# Power.net
KiCad netlist of a schematic drawn in Altium Designer
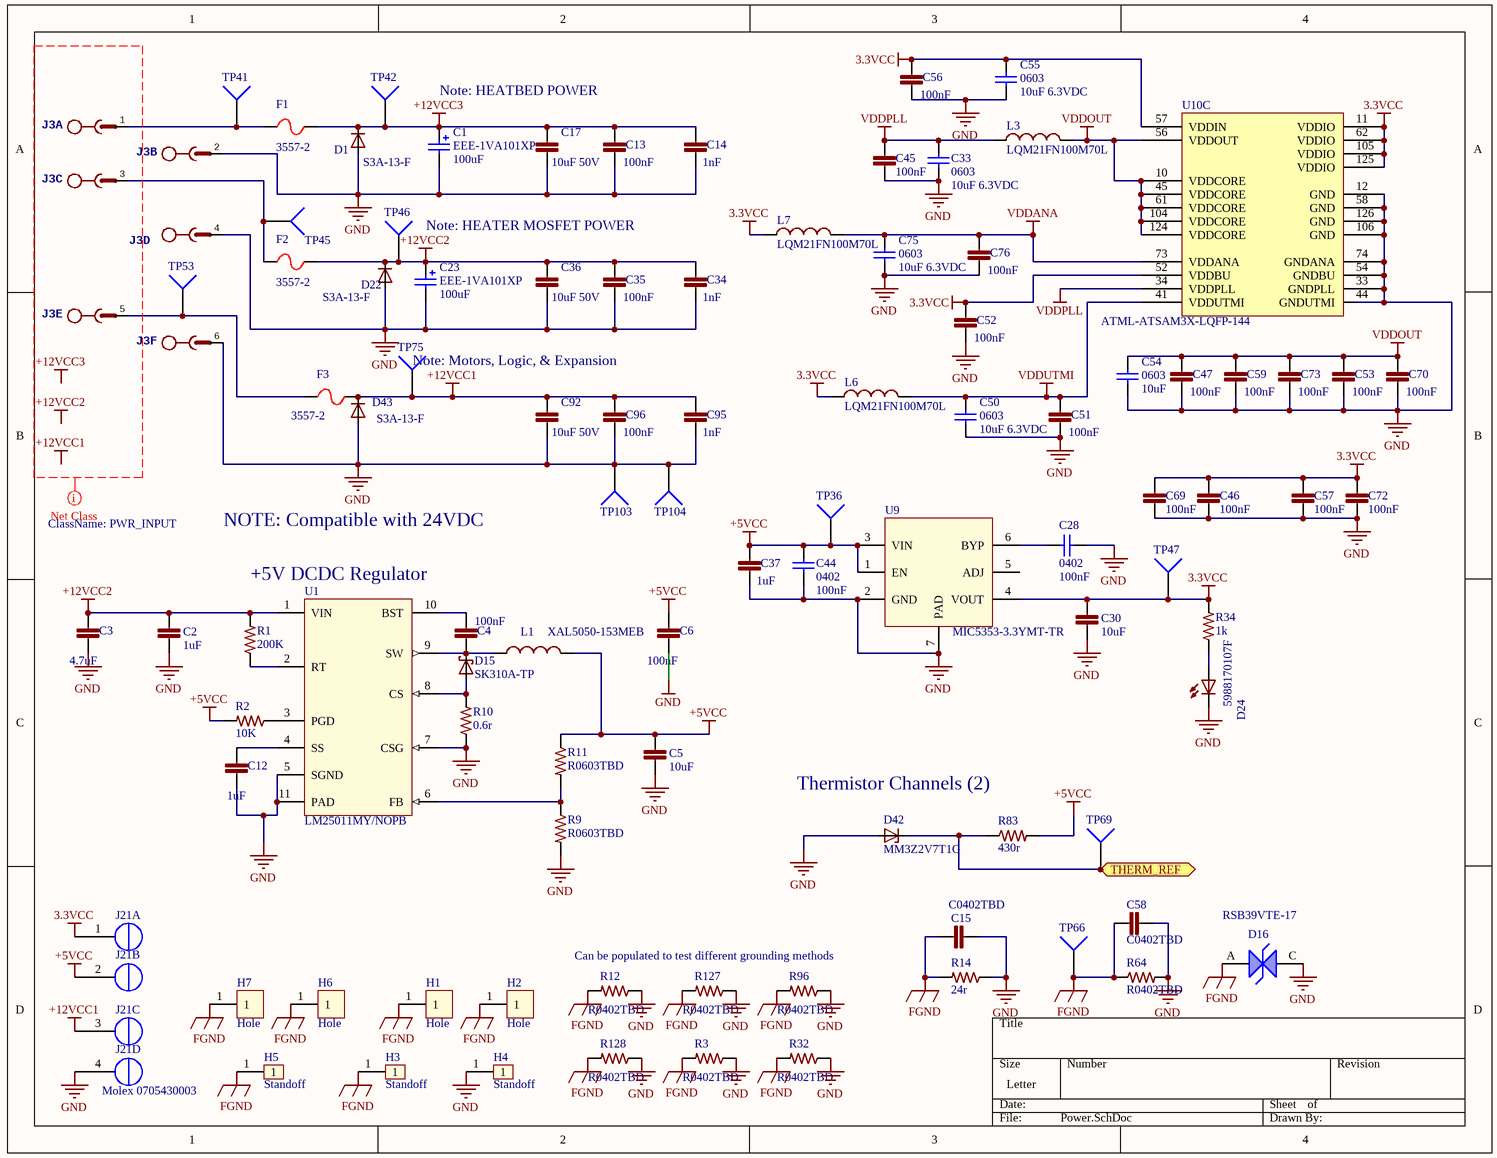
[diagram p0: Power.SchDoc]

(export (version "E")
  (design (tool "Eeschema 10.0.6"))
  (components
    (comp (ref "C1")
      (value "EEE-1VA101XP")
      (footprint "EEE-1VA101XP")
      (description "CAP ALUM 100UF 35V 20% SMD")
      (fields (field (name "DIGIKEY PART #") "PCE3951CT-ND") (field (name "ALTIUM_VALUE") "100uF"))
      (libsource (lib "Tigershark3D") (part "EEE-1VA101XP"))
    )
    (comp (ref "C2")
      (value "1uF")
      (footprint "C0805")
      (description "CAP CER 0805 1uF 50V 10% X7R")
      (fields
        (field (name "MANUFACTURERPARTNUMBER") "GRM21BR71H105KA12L")
        (field (name "PUBLISHER") "UltiMachine")
      )
      (libsource (lib "3Delight") (part "GRM21BR71H105KA12L"))
    )
    (comp (ref "C3")
      (value "4.7uF")
      (footprint "C1206")
      (description "CAP CER 1206 4.7uF 50V 10% X5R")
      (fields
        (field (name "MANUFACTURERPARTNUMBER") "C1206C475K5PACTU")
        (field (name "PUBLISHER") "UltiMachine")
      )
      (libsource (lib "3Delight") (part "C1206C475K5PACTU"))
    )
    (comp (ref "C4")
      (value "100nF")
      (footprint "C0603")
      (description "CAP CER 0603 100nF 50V 10% X7R")
      (fields
        (field (name "MANUFACTURERPARTNUMBER") "C0603C104K5RACTU")
        (field (name "PUBLISHER") "UltiMachine")
      )
      (libsource (lib "3Delight") (part "C0603C104K5RACTU"))
    )
    (comp (ref "C5")
      (value "10uF")
      (footprint "C0805")
      (description "CAP CER 0805 10uF 10V 10% X5R")
      (fields
        (field (name "MANUFACTURERPARTNUMBER") "C0805C106K8PACTU")
        (field (name "PUBLISHER") "UltiMachine")
      )
      (libsource (lib "3Delight") (part "C0805C106K8PACTU"))
    )
    (comp (ref "C6")
      (value "100nF")
      (footprint "C0402")
      (description "CAP CER 0402 100nF 16V 10% X7R")
      (fields
        (field (name "MANUFACTURERPARTNUMBER") "GRM155R71C104KA88D")
        (field (name "PUBLISHER") "UltiMachine")
      )
      (libsource (lib "") (part "GRM155R71C104KA88D_2"))
    )
    (comp (ref "C12")
      (value "1uF")
      (footprint "C0402")
      (description "CAP CER 0402 1uF 6.3V 10% X5R")
      (fields
        (field (name "MANUFACTURERPARTNUMBER") "GRM155R60J105KE19D")
        (field (name "PUBLISHER") "UltiMachine")
      )
      (libsource (lib "3Delight") (part "GRM155R60J105KE19D"))
    )
    (comp (ref "C13")
      (value "100nF")
      (footprint "C0603")
      (description "CAP CER 0603 100nF 50V 10% X7R")
      (fields
        (field (name "MANUFACTURERPARTNUMBER") "C0603C104K5RACTU")
        (field (name "PUBLISHER") "UltiMachine")
      )
      (libsource (lib "3Delight") (part "C0603C104K5RACTU"))
    )
    (comp (ref "C14")
      (value "1nF")
      (footprint "C0603")
      (description "CAP CER 0603  1nF 50v 10% X7R")
      (fields
        (field (name "MANUFACTURERPARTNUMBER") "C0603C102K5RACTU")
        (field (name "PUBLISHER") "UltiMachine")
      )
      (libsource (lib "3Delight") (part "C0603C102K5RACTU"))
    )
    (comp (ref "C15")
      (value "C0402TBD")
      (footprint "C0402")
      (description "Capacitor Non Polarized")
      (fields (field (name "PUBLISHER") "UltiMachine"))
      (libsource (lib "3Delight") (part "C0402TBD"))
    )
    (comp (ref "C17")
      (value "10uF 50V")
      (footprint "C1206")
      (description "CAP CER 10UF 50V 10% X5R 1206")
      (fields
        (field (name "MANUFACTURER") "Samsung")
        (field (name "MANUFACTURERPARTNUMBER") "CL31A106KBHNNNE")
        (field (name "PUBLISHER") "UltiMachine")
      )
      (libsource (lib "Tigershark3D") (part "CL31A106KBHNNNE"))
    )
    (comp (ref "C23")
      (value "EEE-1VA101XP")
      (footprint "EEE-1VA101XP")
      (description "CAP ALUM 100UF 35V 20% SMD")
      (fields (field (name "DIGIKEY PART #") "PCE3951CT-ND") (field (name "ALTIUM_VALUE") "100uF"))
      (libsource (lib "Tigershark3D") (part "EEE-1VA101XP"))
    )
    (comp (ref "C28")
      (value "100nF")
      (footprint "3Delight:C0402")
      (description "Capacitor (Semiconductor SIM Model)")
      (fields
        (field (name "MFR PART #") "GRM155R71C104KA88D")
        (field (name "MFR") "Murata")
        (field (name "PACKAGEREFERENCE") "0402")
        (field (name "PUBLISHER") "Ultimachine")
      )
      (libsource (lib "") (part "GRM155R71C104KA88D_1"))
    )
    (comp (ref "C30")
      (value "10uF")
      (footprint "C0805")
      (description "CAP CER 0805 10uF 10V 10% X5R")
      (fields
        (field (name "MANUFACTURERPARTNUMBER") "C0805C106K8PACTU")
        (field (name "PUBLISHER") "UltiMachine")
      )
      (libsource (lib "3Delight") (part "C0805C106K8PACTU"))
    )
    (comp (ref "C33")
      (value "0603")
      (footprint "C0603")
      (description "CAP CER 10UF 6.3V 10% JB 0603")
      (fields
        (field (name "MFR PART #") "C1608JB0J106K080AB")
        (field (name "MFR") "TDK")
        (field (name "ALTIUM_VALUE") "10uF 6.3VDC")
      )
      (libsource (lib "Tigershark3D") (part "C1608JB0J106K080AB"))
    )
    (comp (ref "C34")
      (value "1nF")
      (footprint "C0603")
      (description "CAP CER 0603  1nF 50v 10% X7R")
      (fields
        (field (name "MANUFACTURERPARTNUMBER") "C0603C102K5RACTU")
        (field (name "PUBLISHER") "UltiMachine")
      )
      (libsource (lib "3Delight") (part "C0603C102K5RACTU"))
    )
    (comp (ref "C35")
      (value "100nF")
      (footprint "C0603")
      (description "CAP CER 0603 100nF 50V 10% X7R")
      (fields
        (field (name "MANUFACTURERPARTNUMBER") "C0603C104K5RACTU")
        (field (name "PUBLISHER") "UltiMachine")
      )
      (libsource (lib "3Delight") (part "C0603C104K5RACTU"))
    )
    (comp (ref "C36")
      (value "10uF 50V")
      (footprint "C1206")
      (description "CAP CER 10UF 50V 10% X5R 1206")
      (fields
        (field (name "MANUFACTURER") "Samsung")
        (field (name "MANUFACTURERPARTNUMBER") "CL31A106KBHNNNE")
        (field (name "PUBLISHER") "UltiMachine")
      )
      (libsource (lib "Tigershark3D") (part "CL31A106KBHNNNE"))
    )
    (comp (ref "C37")
      (value "1uF")
      (footprint "C0402")
      (description "CAP CER 0402 1uF 6.3V 10% X5R")
      (fields
        (field (name "MANUFACTURERPARTNUMBER") "GRM155R60J105KE19D")
        (field (name "PUBLISHER") "UltiMachine")
      )
      (libsource (lib "3Delight") (part "GRM155R60J105KE19D"))
    )
    (comp (ref "C44")
      (value "100nF")
      (footprint "3Delight:C0402")
      (description "Capacitor (Semiconductor SIM Model)")
      (fields
        (field (name "MFR PART #") "GRM155R71C104KA88D")
        (field (name "MFR") "Murata")
        (field (name "PACKAGEREFERENCE") "0402")
        (field (name "PUBLISHER") "Ultimachine")
      )
      (libsource (lib "") (part "GRM155R71C104KA88D_1"))
    )
    (comp (ref "C45")
      (value "100nF")
      (footprint "C0402")
      (description "CAP CER 0402 100nF 16V 10% X7R")
      (fields
        (field (name "MANUFACTURERPARTNUMBER") "GRM155R71C104KA88D")
        (field (name "PUBLISHER") "UltiMachine")
      )
      (libsource (lib "") (part "GRM155R71C104KA88D_3"))
    )
    (comp (ref "C46")
      (value "100nF")
      (footprint "C0402")
      (description "CAP CER 0402 100nF 16V 10% X7R")
      (fields
        (field (name "MANUFACTURERPARTNUMBER") "GRM155R71C104KA88D")
        (field (name "PUBLISHER") "UltiMachine")
      )
      (libsource (lib "") (part "GRM155R71C104KA88D_3"))
    )
    (comp (ref "C47")
      (value "100nF")
      (footprint "C0402")
      (description "CAP CER 0402 100nF 16V 10% X7R")
      (fields
        (field (name "MANUFACTURERPARTNUMBER") "GRM155R71C104KA88D")
        (field (name "PUBLISHER") "UltiMachine")
      )
      (libsource (lib "3Delight") (part "GRM155R71C104KA88D"))
    )
    (comp (ref "C50")
      (value "0603")
      (footprint "C0603")
      (description "CAP CER 10UF 6.3V 10% JB 0603")
      (fields
        (field (name "MFR PART #") "C1608JB0J106K080AB")
        (field (name "MFR") "TDK")
        (field (name "ALTIUM_VALUE") "10uF 6.3VDC")
      )
      (libsource (lib "Tigershark3D") (part "C1608JB0J106K080AB"))
    )
    (comp (ref "C51")
      (value "100nF")
      (footprint "C0402")
      (description "CAP CER 0402 100nF 16V 10% X7R")
      (fields
        (field (name "MANUFACTURERPARTNUMBER") "GRM155R71C104KA88D")
        (field (name "PUBLISHER") "UltiMachine")
      )
      (libsource (lib "3Delight") (part "GRM155R71C104KA88D"))
    )
    (comp (ref "C52")
      (value "100nF")
      (footprint "C0402")
      (description "CAP CER 0402 100nF 16V 10% X7R")
      (fields
        (field (name "MANUFACTURERPARTNUMBER") "GRM155R71C104KA88D")
        (field (name "PUBLISHER") "UltiMachine")
      )
      (libsource (lib "3Delight") (part "GRM155R71C104KA88D"))
    )
    (comp (ref "C53")
      (value "100nF")
      (footprint "C0402")
      (description "CAP CER 0402 100nF 16V 10% X7R")
      (fields
        (field (name "MANUFACTURERPARTNUMBER") "GRM155R71C104KA88D")
        (field (name "PUBLISHER") "UltiMachine")
      )
      (libsource (lib "3Delight") (part "GRM155R71C104KA88D"))
    )
    (comp (ref "C54")
      (value "0603")
      (footprint "C0603")
      (description "CAP CER 10UF 6.3V 10% JB 0603")
      (fields
        (field (name "MFR PART #") "C1608JB0J106K080AB")
        (field (name "MFR") "TDK")
        (field (name "ALTIUM_VALUE") "10uF")
      )
      (libsource (lib "Tigershark3D") (part "C1608JB0J106K080AB"))
    )
    (comp (ref "C55")
      (value "0603")
      (footprint "C0603")
      (description "CAP CER 10UF 6.3V 10% JB 0603")
      (fields
        (field (name "MFR PART #") "C1608JB0J106K080AB")
        (field (name "MFR") "TDK")
        (field (name "ALTIUM_VALUE") "10uF 6.3VDC")
      )
      (libsource (lib "Tigershark3D") (part "C1608JB0J106K080AB"))
    )
    (comp (ref "C56")
      (value "100nF")
      (footprint "C0402")
      (description "CAP CER 0402 100nF 16V 10% X7R")
      (fields
        (field (name "MANUFACTURERPARTNUMBER") "GRM155R71C104KA88D")
        (field (name "PUBLISHER") "UltiMachine")
      )
      (libsource (lib "3Delight") (part "GRM155R71C104KA88D"))
    )
    (comp (ref "C57")
      (value "100nF")
      (footprint "C0402")
      (description "CAP CER 0402 100nF 16V 10% X7R")
      (fields
        (field (name "MANUFACTURERPARTNUMBER") "GRM155R71C104KA88D")
        (field (name "PUBLISHER") "UltiMachine")
      )
      (libsource (lib "") (part "GRM155R71C104KA88D_3"))
    )
    (comp (ref "C58")
      (value "C0402TBD")
      (footprint "C0402")
      (description "Capacitor Non Polarized")
      (fields (field (name "PUBLISHER") "UltiMachine"))
      (libsource (lib "3Delight") (part "C0402TBD"))
    )
    (comp (ref "C59")
      (value "100nF")
      (footprint "C0402")
      (description "CAP CER 0402 100nF 16V 10% X7R")
      (fields
        (field (name "MANUFACTURERPARTNUMBER") "GRM155R71C104KA88D")
        (field (name "PUBLISHER") "UltiMachine")
      )
      (libsource (lib "3Delight") (part "GRM155R71C104KA88D"))
    )
    (comp (ref "C69")
      (value "100nF")
      (footprint "C0402")
      (description "CAP CER 0402 100nF 16V 10% X7R")
      (fields
        (field (name "MANUFACTURERPARTNUMBER") "GRM155R71C104KA88D")
        (field (name "PUBLISHER") "UltiMachine")
      )
      (libsource (lib "") (part "GRM155R71C104KA88D_3"))
    )
    (comp (ref "C70")
      (value "100nF")
      (footprint "C0402")
      (description "CAP CER 0402 100nF 16V 10% X7R")
      (fields
        (field (name "MANUFACTURERPARTNUMBER") "GRM155R71C104KA88D")
        (field (name "PUBLISHER") "UltiMachine")
      )
      (libsource (lib "3Delight") (part "GRM155R71C104KA88D"))
    )
    (comp (ref "C72")
      (value "100nF")
      (footprint "C0402")
      (description "CAP CER 0402 100nF 16V 10% X7R")
      (fields
        (field (name "MANUFACTURERPARTNUMBER") "GRM155R71C104KA88D")
        (field (name "PUBLISHER") "UltiMachine")
      )
      (libsource (lib "") (part "GRM155R71C104KA88D_3"))
    )
    (comp (ref "C73")
      (value "100nF")
      (footprint "C0402")
      (description "CAP CER 0402 100nF 16V 10% X7R")
      (fields
        (field (name "MANUFACTURERPARTNUMBER") "GRM155R71C104KA88D")
        (field (name "PUBLISHER") "UltiMachine")
      )
      (libsource (lib "3Delight") (part "GRM155R71C104KA88D"))
    )
    (comp (ref "C75")
      (value "0603")
      (footprint "C0603")
      (description "CAP CER 10UF 6.3V 10% JB 0603")
      (fields
        (field (name "MFR PART #") "C1608JB0J106K080AB")
        (field (name "MFR") "TDK")
        (field (name "ALTIUM_VALUE") "10uF 6.3VDC")
      )
      (libsource (lib "Tigershark3D") (part "C1608JB0J106K080AB"))
    )
    (comp (ref "C76")
      (value "100nF")
      (footprint "C0402")
      (description "CAP CER 0402 100nF 16V 10% X7R")
      (fields
        (field (name "MANUFACTURERPARTNUMBER") "GRM155R71C104KA88D")
        (field (name "PUBLISHER") "UltiMachine")
      )
      (libsource (lib "3Delight") (part "GRM155R71C104KA88D"))
    )
    (comp (ref "C92")
      (value "10uF 50V")
      (footprint "C1206")
      (description "CAP CER 10UF 50V 10% X5R 1206")
      (fields
        (field (name "MANUFACTURER") "Samsung")
        (field (name "MANUFACTURERPARTNUMBER") "CL31A106KBHNNNE")
        (field (name "PUBLISHER") "UltiMachine")
      )
      (libsource (lib "Tigershark3D") (part "CL31A106KBHNNNE"))
    )
    (comp (ref "C95")
      (value "1nF")
      (footprint "C0603")
      (description "CAP CER 0603  1nF 50v 10% X7R")
      (fields
        (field (name "MANUFACTURERPARTNUMBER") "C0603C102K5RACTU")
        (field (name "PUBLISHER") "UltiMachine")
      )
      (libsource (lib "3Delight") (part "C0603C102K5RACTU"))
    )
    (comp (ref "C96")
      (value "100nF")
      (footprint "C0603")
      (description "CAP CER 0603 100nF 50V 10% X7R")
      (fields
        (field (name "MANUFACTURERPARTNUMBER") "C0603C104K5RACTU")
        (field (name "PUBLISHER") "UltiMachine")
      )
      (libsource (lib "3Delight") (part "C0603C104K5RACTU"))
    )
    (comp (ref "D1")
      (value "S3A-13-F")
      (footprint "DO-214AB")
      (description "DIODE DO-214AB")
      (fields (field (name "PUBLISHER") "UltiMachine"))
      (libsource (lib "3Delight") (part "S3A-13-F"))
    )
    (comp (ref "D15")
      (value "SK310A-TP")
      (footprint "SMA-SM")
      (description "DIODE Schottky 3A SMA")
      (fields (field (name "MANUFACTURERPARTNUMBER") "SK310A") (field (name "PUBLISHER") "UltiMachine"))
      (libsource (lib "3Delight") (part "SK310A"))
    )
    (comp (ref "D16")
      (value "RSB39VTE-17")
      (footprint "SOD323-R")
      (description "DIODE TVS")
      (libsource (lib "3Delight") (part "RSB39VTE-17"))
    )
    (comp (ref "D22")
      (value "S3A-13-F")
      (footprint "DO-214AB")
      (description "DIODE DO-214AB")
      (fields (field (name "PUBLISHER") "UltiMachine"))
      (libsource (lib "3Delight") (part "S3A-13-F"))
    )
    (comp (ref "D24")
      (value "5988170107F")
      (footprint "LED2012120")
      (description "LED 0805 Green")
      (fields (field (name "PUBLISHER") "UltiMachine"))
      (libsource (lib "3Delight") (part "5988170107F"))
    )
    (comp (ref "D42")
      (value "MM3Z2V7T1G")
      (footprint "SOD323-R")
      (description "Z-Diode 2.7V 10mA 200mW")
      (fields (field (name "PUBLISHER") "UltiMachine"))
      (libsource (lib "3Delight") (part "MM3Z2V7T1G"))
    )
    (comp (ref "D43")
      (value "S3A-13-F")
      (footprint "DO-214AB")
      (description "DIODE DO-214AB")
      (fields (field (name "PUBLISHER") "UltiMachine"))
      (libsource (lib "3Delight") (part "S3A-13-F"))
    )
    (comp (ref "F1")
      (value "3557-2")
      (footprint "3557")
      (description "FUSE PTH ATO")
      (fields (field (name "PUBLISHER") "UltiMachine"))
      (libsource (lib "3Delight") (part "3557-2"))
    )
    (comp (ref "F2")
      (value "3557-2")
      (footprint "3557")
      (description "FUSE PTH ATO")
      (fields (field (name "PUBLISHER") "UltiMachine"))
      (libsource (lib "3Delight") (part "3557-2"))
    )
    (comp (ref "F3")
      (value "3557-2")
      (footprint "3557")
      (description "FUSE PTH ATO")
      (fields (field (name "PUBLISHER") "UltiMachine"))
      (libsource (lib "3Delight") (part "3557-2"))
    )
    (comp (ref "H1")
      (value "Hole")
      (footprint "Wave_hole_3x7-singleSided")
      (libsource (lib "3Delight") (part "Hole"))
    )
    (comp (ref "H2")
      (value "Hole")
      (footprint "Wave_hole_3x7-singleSided")
      (libsource (lib "3Delight") (part "Hole"))
    )
    (comp (ref "H3")
      (value "Standoff")
      (footprint "Standoff3mmTopConn")
      (description "Mechanical - Top connect")
      (libsource (lib "3Delight") (part "Standoff3TopConn"))
    )
    (comp (ref "H4")
      (value "Standoff")
      (footprint "Standoff3mmTopConn")
      (description "Mechanical - Top connect")
      (libsource (lib "3Delight") (part "Standoff3TopConn"))
    )
    (comp (ref "H5")
      (value "Standoff")
      (footprint "Standoff3mmTopConn")
      (description "Mechanical - Top connect")
      (libsource (lib "3Delight") (part "Standoff3TopConn"))
    )
    (comp (ref "H6")
      (value "Hole")
      (footprint "Wave_hole_3x7-singleSided")
      (libsource (lib "3Delight") (part "Hole"))
    )
    (comp (ref "H7")
      (value "Hole")
      (footprint "Wave_hole_3x7-singleSided")
      (libsource (lib "3Delight") (part "Hole"))
    )
    (comp (ref "J3")
      (value "MSTBV6")
      (footprint "MSTBV6")
      (description "PHOENIX")
      (fields (field (name "PUBLISHER") "UltiMachine"))
      (libsource (lib "3Delight") (part "MSTBV6"))
    )
    (comp (ref "J21")
      (value "Molex 0705430003")
      (footprint "4POL254")
      (description "Molex 4 Pin Clip Connector")
      (libsource (lib "ZMBo Schematic Library") (part "Molex 0705430003 Alt"))
    )
    (comp (ref "L1")
      (value "XAL5050-153MEB")
      (footprint "XAL50xx-153")
      (description "IND 15uH 3.9A 20%")
      (fields (field (name "PUBLISHER") "UltiMachine"))
      (libsource (lib "3Delight") (part "XAL5050-153MEB"))
    )
    (comp (ref "L3")
      (value "LQM21FN100M70L")
      (footprint "C0805")
      (description "IND 0805 10uH 100mA 780 mOhm 20%")
      (fields (field (name "MANUFACTURERPARTNUMBER") "CBC2012T100M") (field (name "PUBLISHER") "UltiMachine"))
      (libsource (lib "") (part "LQM21FN100M70L_1"))
    )
    (comp (ref "L6")
      (value "LQM21FN100M70L")
      (footprint "C0805")
      (description "IND 0805 10uH 100mA 780 mOhm 20%")
      (fields (field (name "MANUFACTURERPARTNUMBER") "CBC2012T100M") (field (name "PUBLISHER") "UltiMachine"))
      (libsource (lib "3Delight") (part "LQM21FN100M70L"))
    )
    (comp (ref "L7")
      (value "LQM21FN100M70L")
      (footprint "C0805")
      (description "IND 0805 10uH 100mA 780 mOhm 20%")
      (fields (field (name "MANUFACTURERPARTNUMBER") "CBC2012T100M") (field (name "PUBLISHER") "UltiMachine"))
      (libsource (lib "3Delight") (part "LQM21FN100M70L"))
    )
    (comp (ref "R1")
      (value "200K")
      (footprint "R0402")
      (description "RES 0402 200k 63mW 1%")
      (fields
        (field (name "MANUFACTURERPARTNUMBER") "CRCW0402200KFKED")
        (field (name "PUBLISHER") "UltiMachine")
      )
      (libsource (lib "3Delight") (part "CRCW0402200KFKED"))
    )
    (comp (ref "R2")
      (value "10K")
      (footprint "R0402")
      (description "RES SMD 10K OHM 1% 1/16W 0402")
      (fields
        (field (name "MANUFACTURERPARTNUMBER") "RC0402FR-0710KP")
        (field (name "PUBLISHER") "UltiMachine")
      )
      (libsource (lib "3Delight") (part "RC0402FR-0710KP"))
    )
    (comp (ref "R3")
      (value "R0402TBD")
      (footprint "R0402")
      (description "Resistor")
      (fields (field (name "PUBLISHER") "UltiMachine"))
      (libsource (lib "3Delight") (part "R0402TBD"))
    )
    (comp (ref "R9")
      (value "R0603TBD")
      (footprint "R0603")
      (description "Resistor")
      (fields (field (name "PUBLISHER") "UltiMachine"))
      (libsource (lib "3Delight") (part "R0603TBD"))
    )
    (comp (ref "R10")
      (value "0.6r")
      (footprint "2512R-0.55")
      (description "RES 0.06 OHM 1W 1% 2512 SMD")
      (fields
        (field (name "MANUFACTURERPARTNUMBER") "RL2512FK-070R06L")
        (field (name "PUBLISHER") "UltiMachine")
      )
      (libsource (lib "3Delight") (part "RL2512FK-070R06L"))
    )
    (comp (ref "R11")
      (value "R0603TBD")
      (footprint "R0603")
      (description "Resistor")
      (fields (field (name "PUBLISHER") "UltiMachine"))
      (libsource (lib "3Delight") (part "R0603TBD"))
    )
    (comp (ref "R12")
      (value "R0402TBD")
      (footprint "R0402")
      (description "Resistor")
      (fields (field (name "PUBLISHER") "UltiMachine"))
      (libsource (lib "3Delight") (part "R0402TBD"))
    )
    (comp (ref "R14")
      (value "24r")
      (footprint "R0402")
      (description "Res Thick Film 0402 24 Ohm 1% 0.063W")
      (fields
        (field (name "MANUFACTURERPARTNUMBER") "CRCW0402200KFKED")
        (field (name "PUBLISHER") "UltiMachine")
      )
      (libsource (lib "3Delight") (part "CRCW040224R0FKED"))
    )
    (comp (ref "R32")
      (value "R0402TBD")
      (footprint "R0402")
      (description "Resistor")
      (fields (field (name "PUBLISHER") "UltiMachine"))
      (libsource (lib "3Delight") (part "R0402TBD"))
    )
    (comp (ref "R34")
      (value "1k")
      (footprint "R0402")
      (description "RES 0402 1k 63mW 1%")
      (fields (field (name "PUBLISHER") "UltiMachine"))
      (libsource (lib "3Delight") (part "RK73H1ETTP1001F"))
    )
    (comp (ref "R64")
      (value "R0402TBD")
      (footprint "R0402")
      (description "Resistor")
      (fields (field (name "PUBLISHER") "UltiMachine"))
      (libsource (lib "3Delight") (part "R0402TBD"))
    )
    (comp (ref "R83")
      (value "430r")
      (footprint "R0603")
      (description "RES 0603 0.1 W 430 Ohms 5% ±100 ppm/°C SMT")
      (fields
        (field (name "MANUFACTURERPARTNUMBER") "RC0603JR-07430RL")
        (field (name "PUBLISHER") "UltiMachine")
      )
      (libsource (lib "3Delight") (part "RC0603JR-07430RL"))
    )
    (comp (ref "R96")
      (value "R0402TBD")
      (footprint "R0402")
      (description "Resistor")
      (fields (field (name "PUBLISHER") "UltiMachine"))
      (libsource (lib "3Delight") (part "R0402TBD"))
    )
    (comp (ref "R127")
      (value "R0402TBD")
      (footprint "R0402")
      (description "Resistor")
      (fields (field (name "PUBLISHER") "UltiMachine"))
      (libsource (lib "3Delight") (part "R0402TBD"))
    )
    (comp (ref "R128")
      (value "R0402TBD")
      (footprint "R0402")
      (description "Resistor")
      (fields (field (name "PUBLISHER") "UltiMachine"))
      (libsource (lib "3Delight") (part "R0402TBD"))
    )
    (comp (ref "TP36")
      (value "TP4")
      (footprint "TP-2")
      (description "Socket")
      (fields (field (name "PUBLISHER") "Altium Limited"))
      (libsource (lib "ZMBo Schematic Library") (part "Socket"))
    )
    (comp (ref "TP41")
      (value "TP4")
      (footprint "TP-2")
      (description "Socket")
      (fields (field (name "PUBLISHER") "Altium Limited"))
      (libsource (lib "ZMBo Schematic Library") (part "Socket"))
    )
    (comp (ref "TP42")
      (value "TP4")
      (footprint "TP-2")
      (description "Socket")
      (fields (field (name "PUBLISHER") "Altium Limited"))
      (libsource (lib "ZMBo Schematic Library") (part "Socket"))
    )
    (comp (ref "TP45")
      (value "TP4")
      (footprint "TP-2")
      (description "Socket")
      (fields (field (name "PUBLISHER") "Altium Limited"))
      (libsource (lib "ZMBo Schematic Library") (part "Socket"))
    )
    (comp (ref "TP46")
      (value "TP4")
      (footprint "TP-2")
      (description "Socket")
      (fields (field (name "PUBLISHER") "Altium Limited"))
      (libsource (lib "ZMBo Schematic Library") (part "Socket"))
    )
    (comp (ref "TP47")
      (value "TP4")
      (footprint "TP-2")
      (description "Socket")
      (fields (field (name "PUBLISHER") "Altium Limited"))
      (libsource (lib "ZMBo Schematic Library") (part "Socket"))
    )
    (comp (ref "TP53")
      (value "TP4")
      (footprint "TP-2")
      (description "Socket")
      (fields (field (name "PUBLISHER") "Altium Limited"))
      (libsource (lib "ZMBo Schematic Library") (part "Socket"))
    )
    (comp (ref "TP66")
      (value "TP4")
      (footprint "TP-2")
      (description "Socket")
      (fields (field (name "PUBLISHER") "Altium Limited"))
      (libsource (lib "ZMBo Schematic Library") (part "Socket"))
    )
    (comp (ref "TP69")
      (value "TP4")
      (footprint "TP-2")
      (description "Socket")
      (fields (field (name "PUBLISHER") "Altium Limited"))
      (libsource (lib "ZMBo Schematic Library") (part "Socket"))
    )
    (comp (ref "TP75")
      (value "TP4")
      (footprint "TP-2")
      (description "Socket")
      (fields (field (name "PUBLISHER") "Altium Limited"))
      (libsource (lib "ZMBo Schematic Library") (part "Socket"))
    )
    (comp (ref "TP103")
      (value "TP4")
      (footprint "TP-2")
      (description "Socket")
      (fields (field (name "PUBLISHER") "Altium Limited"))
      (libsource (lib "ZMBo Schematic Library") (part "Socket"))
    )
    (comp (ref "TP104")
      (value "TP4")
      (footprint "TP-2")
      (description "Socket")
      (fields (field (name "PUBLISHER") "Altium Limited"))
      (libsource (lib "ZMBo Schematic Library") (part "Socket"))
    )
    (comp (ref "U1")
      (value "LM25011MY/NOPB")
      (footprint "VSSOP10")
      (description "REG BUCK")
      (libsource (lib "3Delight") (part "LM25011"))
    )
    (comp (ref "U9")
      (value "MIC5353-3.3YMT-TR")
      (footprint "TDFN1616-6LD-PL-1")
      (description "LDO 3.3V 500mA - low ESR Cout")
      (libsource (lib "Tigershark3D") (part "MIC5353-3.3YMT-TR"))
    )
    (comp (ref "U10")
      (value "ATML-ATSAM3X-LQFP-144")
      (footprint "LQFP144_N")
      (libsource (lib "ZMBo Schematic Library") (part "ATML-ATSAM3X-LQFP-144"))
    )
  )
  (nets
    (net (code "1") (name "+5VCC") (class "Default")
      (node (ref "C37") (pin "1") (pinfunction "1_1") (pintype "passive"))
      (node (ref "C44") (pin "1") (pinfunction "1_1") (pintype "passive"))
      (node (ref "C5") (pin "1") (pinfunction "1_1") (pintype "passive"))
      (node (ref "C6") (pin "2") (pinfunction "2_2") (pintype "passive"))
      (node (ref "J21") (pin "2") (pinfunction "OUT2A_2") (pintype "passive"))
      (node (ref "L1") (pin "2") (pinfunction "2_2") (pintype "passive"))
      (node (ref "R11") (pin "1") (pinfunction "1_1") (pintype "passive"))
      (node (ref "R2") (pin "2") (pinfunction "2_2") (pintype "passive"))
      (node (ref "R83") (pin "2") (pinfunction "2_2") (pintype "passive"))
      (node (ref "TP36") (pin "1") (pinfunction "1_1") (pintype "passive"))
      (node (ref "U9") (pin "1") (pinfunction "EN_1") (pintype "power_in"))
      (node (ref "U9") (pin "3") (pinfunction "VIN_3") (pintype "power_in"))
    )
    (net (code "2") (name "+12VCC1") (class "Default")
      (node (ref "C92") (pin "1") (pinfunction "1_1") (pintype "passive"))
      (node (ref "C95") (pin "1") (pinfunction "1_1") (pintype "passive"))
      (node (ref "C96") (pin "1") (pinfunction "1_1") (pintype "passive"))
      (node (ref "D43") (pin "C") (pinfunction "C_C") (pintype "passive"))
      (node (ref "F3") (pin "2") (pinfunction "2_2") (pintype "passive"))
      (node (ref "J21") (pin "3") (pinfunction "OUT1A_3") (pintype "passive"))
      (node (ref "TP75") (pin "1") (pinfunction "1_1") (pintype "passive"))
    )
    (net (code "3") (name "+12VCC2") (class "Default")
      (node (ref "C2") (pin "1") (pinfunction "1_1") (pintype "passive"))
      (node (ref "C23") (pin "1") (pinfunction "1_1") (pintype "passive"))
      (node (ref "C3") (pin "1") (pinfunction "1_1") (pintype "passive"))
      (node (ref "C34") (pin "1") (pinfunction "1_1") (pintype "passive"))
      (node (ref "C35") (pin "1") (pinfunction "1_1") (pintype "passive"))
      (node (ref "C36") (pin "1") (pinfunction "1_1") (pintype "passive"))
      (node (ref "D22") (pin "C") (pinfunction "C_C") (pintype "passive"))
      (node (ref "F2") (pin "2") (pinfunction "2_2") (pintype "passive"))
      (node (ref "R1") (pin "2") (pinfunction "2_2") (pintype "passive"))
      (node (ref "TP46") (pin "1") (pinfunction "1_1") (pintype "passive"))
      (node (ref "U1") (pin "1") (pinfunction "VIN_1") (pintype "power_in"))
    )
    (net (code "4") (name "+12VCC3") (class "Default")
      (node (ref "C1") (pin "1") (pinfunction "1_1") (pintype "passive"))
      (node (ref "C13") (pin "1") (pinfunction "1_1") (pintype "passive"))
      (node (ref "C14") (pin "1") (pinfunction "1_1") (pintype "passive"))
      (node (ref "C17") (pin "1") (pinfunction "1_1") (pintype "passive"))
      (node (ref "D1") (pin "C") (pinfunction "C_C") (pintype "passive"))
      (node (ref "F1") (pin "2") (pinfunction "2_2") (pintype "passive"))
      (node (ref "TP42") (pin "1") (pinfunction "1_1") (pintype "passive"))
    )
    (net (code "5") (name "/THERM_REF") (class "Default")
      (node (ref "D42") (pin "C") (pinfunction "C_C") (pintype "passive"))
      (node (ref "R83") (pin "1") (pinfunction "1_1") (pintype "passive"))
      (node (ref "TP69") (pin "1") (pinfunction "1_1") (pintype "passive"))
    )
    (net (code "6") (name "3.3VCC") (class "Default")
      (node (ref "C30") (pin "1") (pinfunction "1_1") (pintype "passive"))
      (node (ref "C46") (pin "1") (pinfunction "1_1") (pintype "passive"))
      (node (ref "C52") (pin "1") (pinfunction "1_1") (pintype "passive"))
      (node (ref "C55") (pin "2") (pinfunction "2_2") (pintype "passive"))
      (node (ref "C56") (pin "1") (pinfunction "1_1") (pintype "passive"))
      (node (ref "C57") (pin "1") (pinfunction "1_1") (pintype "passive"))
      (node (ref "C69") (pin "1") (pinfunction "1_1") (pintype "passive"))
      (node (ref "C72") (pin "1") (pinfunction "1_1") (pintype "passive"))
      (node (ref "J21") (pin "1") (pinfunction "OUT2B_1") (pintype "passive"))
      (node (ref "L6") (pin "1") (pinfunction "1_1") (pintype "passive"))
      (node (ref "L7") (pin "1") (pinfunction "1_1") (pintype "passive"))
      (node (ref "R34") (pin "2") (pinfunction "2_2") (pintype "passive"))
      (node (ref "TP47") (pin "1") (pinfunction "1_1") (pintype "passive"))
      (node (ref "U10") (pin "105") (pinfunction "VDDIO_105") (pintype "power_in"))
      (node (ref "U10") (pin "11") (pinfunction "VDDIO_11") (pintype "power_in"))
      (node (ref "U10") (pin "125") (pinfunction "VDDIO_125") (pintype "power_in"))
      (node (ref "U10") (pin "52") (pinfunction "VDDBU_52") (pintype "power_in"))
      (node (ref "U10") (pin "57") (pinfunction "VDDIN_57") (pintype "power_in"))
      (node (ref "U10") (pin "62") (pinfunction "VDDIO_62") (pintype "power_in"))
      (node (ref "U9") (pin "4") (pinfunction "VOUT_4") (pintype "power_in"))
    )
    (net (code "7") (name "FGND") (class "Default")
      (node (ref "C15") (pin "1") (pinfunction "1_1") (pintype "passive"))
      (node (ref "C58") (pin "1") (pinfunction "1_1") (pintype "passive"))
      (node (ref "D16") (pin "A") (pinfunction "A_A") (pintype "power_in"))
      (node (ref "H1") (pin "1") (pinfunction "1_1") (pintype "power_in"))
      (node (ref "H2") (pin "1") (pinfunction "1_1") (pintype "power_in"))
      (node (ref "H3") (pin "1") (pinfunction "1_1") (pintype "power_in"))
      (node (ref "H5") (pin "1") (pinfunction "1_1") (pintype "power_in"))
      (node (ref "H6") (pin "1") (pinfunction "1_1") (pintype "power_in"))
      (node (ref "H7") (pin "1") (pinfunction "1_1") (pintype "power_in"))
      (node (ref "R12") (pin "2") (pinfunction "2_2") (pintype "passive"))
      (node (ref "R127") (pin "2") (pinfunction "2_2") (pintype "passive"))
      (node (ref "R128") (pin "2") (pinfunction "2_2") (pintype "passive"))
      (node (ref "R14") (pin "2") (pinfunction "2_2") (pintype "passive"))
      (node (ref "R3") (pin "2") (pinfunction "2_2") (pintype "passive"))
      (node (ref "R32") (pin "2") (pinfunction "2_2") (pintype "passive"))
      (node (ref "R64") (pin "1") (pinfunction "1_1") (pintype "passive"))
      (node (ref "R96") (pin "2") (pinfunction "2_2") (pintype "passive"))
      (node (ref "TP66") (pin "1") (pinfunction "1_1") (pintype "passive"))
    )
    (net (code "8") (name "GND") (class "Default")
      (node (ref "C1") (pin "2") (pinfunction "2_2") (pintype "passive"))
      (node (ref "C12") (pin "2") (pinfunction "2_2") (pintype "passive"))
      (node (ref "C13") (pin "2") (pinfunction "2_2") (pintype "passive"))
      (node (ref "C14") (pin "2") (pinfunction "2_2") (pintype "passive"))
      (node (ref "C15") (pin "2") (pinfunction "2_2") (pintype "passive"))
      (node (ref "C17") (pin "2") (pinfunction "2_2") (pintype "passive"))
      (node (ref "C2") (pin "2") (pinfunction "2_2") (pintype "passive"))
      (node (ref "C23") (pin "2") (pinfunction "2_2") (pintype "passive"))
      (node (ref "C28") (pin "2") (pinfunction "2_2") (pintype "passive"))
      (node (ref "C3") (pin "2") (pinfunction "2_2") (pintype "passive"))
      (node (ref "C30") (pin "2") (pinfunction "2_2") (pintype "passive"))
      (node (ref "C33") (pin "1") (pinfunction "1_1") (pintype "passive"))
      (node (ref "C34") (pin "2") (pinfunction "2_2") (pintype "passive"))
      (node (ref "C35") (pin "2") (pinfunction "2_2") (pintype "passive"))
      (node (ref "C36") (pin "2") (pinfunction "2_2") (pintype "passive"))
      (node (ref "C37") (pin "2") (pinfunction "2_2") (pintype "passive"))
      (node (ref "C44") (pin "2") (pinfunction "2_2") (pintype "passive"))
      (node (ref "C45") (pin "2") (pinfunction "2_2") (pintype "passive"))
      (node (ref "C46") (pin "2") (pinfunction "2_2") (pintype "passive"))
      (node (ref "C47") (pin "2") (pinfunction "2_2") (pintype "passive"))
      (node (ref "C5") (pin "2") (pinfunction "2_2") (pintype "passive"))
      (node (ref "C50") (pin "1") (pinfunction "1_1") (pintype "passive"))
      (node (ref "C51") (pin "2") (pinfunction "2_2") (pintype "passive"))
      (node (ref "C52") (pin "2") (pinfunction "2_2") (pintype "passive"))
      (node (ref "C53") (pin "2") (pinfunction "2_2") (pintype "passive"))
      (node (ref "C54") (pin "1") (pinfunction "1_1") (pintype "passive"))
      (node (ref "C55") (pin "1") (pinfunction "1_1") (pintype "passive"))
      (node (ref "C56") (pin "2") (pinfunction "2_2") (pintype "passive"))
      (node (ref "C57") (pin "2") (pinfunction "2_2") (pintype "passive"))
      (node (ref "C58") (pin "2") (pinfunction "2_2") (pintype "passive"))
      (node (ref "C59") (pin "2") (pinfunction "2_2") (pintype "passive"))
      (node (ref "C6") (pin "1") (pinfunction "1_1") (pintype "passive"))
      (node (ref "C69") (pin "2") (pinfunction "2_2") (pintype "passive"))
      (node (ref "C70") (pin "2") (pinfunction "2_2") (pintype "passive"))
      (node (ref "C72") (pin "2") (pinfunction "2_2") (pintype "passive"))
      (node (ref "C73") (pin "2") (pinfunction "2_2") (pintype "passive"))
      (node (ref "C75") (pin "1") (pinfunction "1_1") (pintype "passive"))
      (node (ref "C76") (pin "2") (pinfunction "2_2") (pintype "passive"))
      (node (ref "C92") (pin "2") (pinfunction "2_2") (pintype "passive"))
      (node (ref "C95") (pin "2") (pinfunction "2_2") (pintype "passive"))
      (node (ref "C96") (pin "2") (pinfunction "2_2") (pintype "passive"))
      (node (ref "D1") (pin "A") (pinfunction "A_A") (pintype "passive"))
      (node (ref "D16") (pin "C") (pinfunction "C_C") (pintype "power_in"))
      (node (ref "D22") (pin "A") (pinfunction "A_A") (pintype "passive"))
      (node (ref "D24") (pin "C") (pinfunction "C_C") (pintype "passive"))
      (node (ref "D42") (pin "A") (pinfunction "A_A") (pintype "passive"))
      (node (ref "D43") (pin "A") (pinfunction "A_A") (pintype "passive"))
      (node (ref "H4") (pin "1") (pinfunction "1_1") (pintype "power_in"))
      (node (ref "J21") (pin "4") (pinfunction "OUT1B_4") (pintype "passive"))
      (node (ref "J3") (pin "2") (pinfunction "1_2") (pintype "passive"))
      (node (ref "J3") (pin "4") (pinfunction "1_4") (pintype "passive"))
      (node (ref "J3") (pin "6") (pinfunction "1_6") (pintype "passive"))
      (node (ref "R10") (pin "1") (pinfunction "1_1") (pintype "passive"))
      (node (ref "R12") (pin "1") (pinfunction "1_1") (pintype "passive"))
      (node (ref "R127") (pin "1") (pinfunction "1_1") (pintype "passive"))
      (node (ref "R128") (pin "1") (pinfunction "1_1") (pintype "passive"))
      (node (ref "R14") (pin "1") (pinfunction "1_1") (pintype "passive"))
      (node (ref "R3") (pin "1") (pinfunction "1_1") (pintype "passive"))
      (node (ref "R32") (pin "1") (pinfunction "1_1") (pintype "passive"))
      (node (ref "R64") (pin "2") (pinfunction "2_2") (pintype "passive"))
      (node (ref "R9") (pin "2") (pinfunction "2_2") (pintype "passive"))
      (node (ref "R96") (pin "1") (pinfunction "1_1") (pintype "passive"))
      (node (ref "TP103") (pin "1") (pinfunction "1_1") (pintype "passive"))
      (node (ref "TP104") (pin "1") (pinfunction "1_1") (pintype "passive"))
      (node (ref "U1") (pin "11") (pinfunction "PAD_11") (pintype "power_in"))
      (node (ref "U1") (pin "5") (pinfunction "SGND_5") (pintype "power_in"))
      (node (ref "U1") (pin "7") (pinfunction "CSG_7") (pintype "input"))
      (node (ref "U10") (pin "106") (pinfunction "GND_106") (pintype "power_in"))
      (node (ref "U10") (pin "12") (pinfunction "GND_12") (pintype "power_in"))
      (node (ref "U10") (pin "126") (pinfunction "GND_126") (pintype "power_in"))
      (node (ref "U10") (pin "33") (pinfunction "GNDPLL_33") (pintype "power_in"))
      (node (ref "U10") (pin "44") (pinfunction "GNDUTMI_44") (pintype "power_in"))
      (node (ref "U10") (pin "54") (pinfunction "GNDBU_54") (pintype "power_in"))
      (node (ref "U10") (pin "58") (pinfunction "GND_58") (pintype "power_in"))
      (node (ref "U10") (pin "74") (pinfunction "GNDANA_74") (pintype "power_in"))
      (node (ref "U9") (pin "2") (pinfunction "GND_2") (pintype "power_in"))
      (node (ref "U9") (pin "7") (pinfunction "PAD_7") (pintype "power_in"))
    )
    (net (code "9") (name "Net-(D24-PadA)") (class "Default")
      (node (ref "D24") (pin "A") (pinfunction "A_A") (pintype "passive"))
      (node (ref "R34") (pin "1") (pinfunction "1_1") (pintype "passive"))
    )
    (net (code "10") (name "Net-(F1-Pad1)") (class "Default")
      (node (ref "F1") (pin "1") (pinfunction "1_1") (pintype "passive"))
      (node (ref "J3") (pin "1") (pinfunction "1_1") (pintype "passive"))
      (node (ref "TP41") (pin "1") (pinfunction "1_1") (pintype "passive"))
    )
    (net (code "11") (name "Net-(J3C-1)") (class "Default")
      (node (ref "F2") (pin "1") (pinfunction "1_1") (pintype "passive"))
      (node (ref "J3") (pin "3") (pinfunction "1_3") (pintype "passive"))
      (node (ref "TP45") (pin "1") (pinfunction "1_1") (pintype "passive"))
    )
    (net (code "12") (name "Net-(J3E-1)") (class "Default")
      (node (ref "F3") (pin "1") (pinfunction "1_1") (pintype "passive"))
      (node (ref "J3") (pin "5") (pinfunction "1_5") (pintype "passive"))
      (node (ref "TP53") (pin "1") (pinfunction "1_1") (pintype "passive"))
    )
    (net (code "13") (name "Net-(U1-BST)") (class "Default")
      (node (ref "C4") (pin "1") (pinfunction "1_1") (pintype "passive"))
      (node (ref "U1") (pin "10") (pinfunction "BST_10") (pintype "power_in"))
    )
    (net (code "14") (name "Net-(U1-CS)") (class "Default")
      (node (ref "D15") (pin "A") (pinfunction "A_A") (pintype "passive"))
      (node (ref "R10") (pin "2") (pinfunction "2_2") (pintype "passive"))
      (node (ref "U1") (pin "8") (pinfunction "CS_8") (pintype "input"))
    )
    (net (code "15") (name "Net-(U1-FB)") (class "Default")
      (node (ref "R11") (pin "2") (pinfunction "2_2") (pintype "passive"))
      (node (ref "R9") (pin "1") (pinfunction "1_1") (pintype "passive"))
      (node (ref "U1") (pin "6") (pinfunction "FB_6") (pintype "input"))
    )
    (net (code "16") (name "Net-(U1-PGD)") (class "Default")
      (node (ref "R2") (pin "1") (pinfunction "1_1") (pintype "passive"))
      (node (ref "U1") (pin "3") (pinfunction "PGD_3") (pintype "power_in"))
    )
    (net (code "17") (name "Net-(U1-RT)") (class "Default")
      (node (ref "R1") (pin "1") (pinfunction "1_1") (pintype "passive"))
      (node (ref "U1") (pin "2") (pinfunction "RT_2") (pintype "power_in"))
    )
    (net (code "18") (name "Net-(U1-SS)") (class "Default")
      (node (ref "C12") (pin "1") (pinfunction "1_1") (pintype "passive"))
      (node (ref "U1") (pin "4") (pinfunction "SS_4") (pintype "power_in"))
    )
    (net (code "19") (name "Net-(U1-SW)") (class "Default")
      (node (ref "C4") (pin "2") (pinfunction "2_2") (pintype "passive"))
      (node (ref "D15") (pin "C") (pinfunction "C_C") (pintype "passive"))
      (node (ref "L1") (pin "1") (pinfunction "1_1") (pintype "passive"))
      (node (ref "U1") (pin "9") (pinfunction "SW_9") (pintype "output"))
    )
    (net (code "20") (name "Net-(U9-BYP)") (class "Default")
      (node (ref "C28") (pin "1") (pinfunction "1_1") (pintype "passive"))
      (node (ref "U9") (pin "6") (pinfunction "BYP_6") (pintype "power_in"))
    )
    (net (code "21") (name "VDDANA") (class "Default")
      (node (ref "C75") (pin "2") (pinfunction "2_2") (pintype "passive"))
      (node (ref "C76") (pin "1") (pinfunction "1_1") (pintype "passive"))
      (node (ref "L7") (pin "2") (pinfunction "2_2") (pintype "passive"))
      (node (ref "U10") (pin "73") (pinfunction "VDDANA_73") (pintype "power_in"))
    )
    (net (code "22") (name "VDDOUT") (class "Default")
      (node (ref "C47") (pin "1") (pinfunction "1_1") (pintype "passive"))
      (node (ref "C53") (pin "1") (pinfunction "1_1") (pintype "passive"))
      (node (ref "C54") (pin "2") (pinfunction "2_2") (pintype "passive"))
      (node (ref "C59") (pin "1") (pinfunction "1_1") (pintype "passive"))
      (node (ref "C70") (pin "1") (pinfunction "1_1") (pintype "passive"))
      (node (ref "C73") (pin "1") (pinfunction "1_1") (pintype "passive"))
      (node (ref "L3") (pin "1") (pinfunction "1_1") (pintype "passive"))
      (node (ref "U10") (pin "10") (pinfunction "VDDCORE_10") (pintype "power_in"))
      (node (ref "U10") (pin "104") (pinfunction "VDDCORE_104") (pintype "power_in"))
      (node (ref "U10") (pin "124") (pinfunction "VDDCORE_124") (pintype "power_in"))
      (node (ref "U10") (pin "45") (pinfunction "VDDCORE_45") (pintype "power_in"))
      (node (ref "U10") (pin "56") (pinfunction "VDDOUT_56") (pintype "power_in"))
      (node (ref "U10") (pin "61") (pinfunction "VDDCORE_61") (pintype "power_in"))
    )
    (net (code "23") (name "VDDPLL") (class "Default")
      (node (ref "C33") (pin "2") (pinfunction "2_2") (pintype "passive"))
      (node (ref "C45") (pin "1") (pinfunction "1_1") (pintype "passive"))
      (node (ref "L3") (pin "2") (pinfunction "2_2") (pintype "passive"))
      (node (ref "U10") (pin "34") (pinfunction "VDDPLL_34") (pintype "power_in"))
    )
    (net (code "24") (name "VDDUTMI") (class "Default")
      (node (ref "C50") (pin "2") (pinfunction "2_2") (pintype "passive"))
      (node (ref "C51") (pin "1") (pinfunction "1_1") (pintype "passive"))
      (node (ref "L6") (pin "2") (pinfunction "2_2") (pintype "passive"))
      (node (ref "U10") (pin "41") (pinfunction "VDDUTMI_41") (pintype "power_in"))
    )
    (net (code "25") (name "unconnected-(U9-ADJ-Pad5)") (class "Default")
      (node (ref "U9") (pin "5") (pinfunction "ADJ_5") (pintype "power_in"))
    )
  )
)
